# RFSens.net
KiCad netlist of a schematic drawn in EAGLE
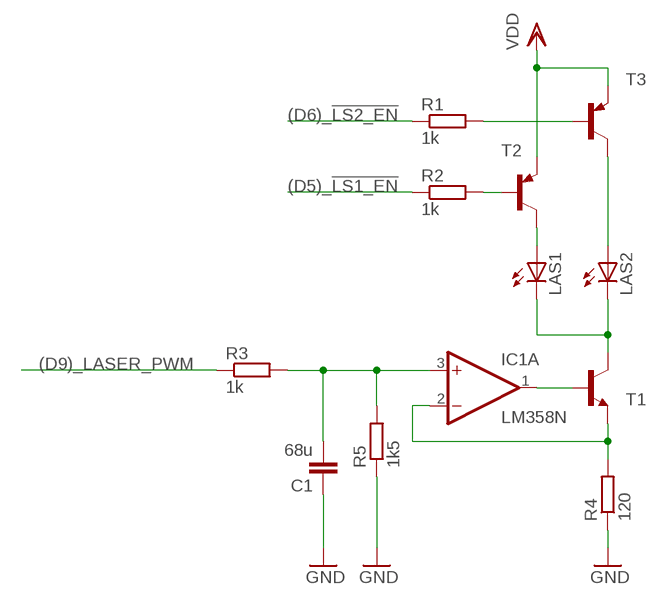
[diagram p0: schematic, sheet 1]

(export (version "E")
  (design (tool "Eeschema 10.0.6"))
  (components
    (comp (ref "C1")
      (value "68u")
      (footprint "eagle-import:C5B3.5")
      (libsource (lib "eagle-import") (part "C5/3.5"))
    )
    (comp (ref "IC1")
      (value "LM358N")
      (footprint "eagle-import:DIL08")
      (libsource (lib "eagle-import") (part "LM358N"))
    )
    (comp (ref "LAS1")
      (value "LED")
      (footprint "eagle-import:SMARTLED-TTW")
      (libsource (lib "eagle-import") (part "LED"))
    )
    (comp (ref "LAS2")
      (value "LED")
      (footprint "eagle-import:SMARTLED-TTW")
      (libsource (lib "eagle-import") (part "LED"))
    )
    (comp (ref "R1")
      (value "1k")
      (footprint "eagle-import:0204_5")
      (libsource (lib "eagle-import") (part "R-EU_0204/5"))
    )
    (comp (ref "R2")
      (value "1k")
      (footprint "eagle-import:0204_5")
      (libsource (lib "eagle-import") (part "R-EU_0204/5"))
    )
    (comp (ref "R3")
      (value "1k")
      (footprint "eagle-import:0204_5")
      (libsource (lib "eagle-import") (part "R-EU_0204/5"))
    )
    (comp (ref "R4")
      (value "120")
      (footprint "eagle-import:0204_5")
      (libsource (lib "eagle-import") (part "R-EU_0204/5"))
    )
    (comp (ref "R5")
      (value "1k5")
      (footprint "eagle-import:0204_5")
      (libsource (lib "eagle-import") (part "R-EU_0204/5"))
    )
    (comp (ref "T1")
      (value "-NPN-SOT89-BCE")
      (footprint "eagle-import:SOT89-BCE")
      (libsource (lib "eagle-import") (part "-NPN-SOT89-BCE"))
    )
    (comp (ref "T2")
      (value "-PNP-SOT23-EBC")
      (footprint "eagle-import:SOT23-EBC")
      (libsource (lib "eagle-import") (part "-PNP-SOT23-EBC"))
    )
    (comp (ref "T3")
      (value "-PNP-SOT23-EBC")
      (footprint "eagle-import:SOT23-EBC")
      (libsource (lib "eagle-import") (part "-PNP-SOT23-EBC"))
    )
  )
  (nets
    (net (code "1") (name "/(D5)_~{LS1_EN}") (class "Default")
      (node (ref "R2") (pin "1") (pinfunction "1_1") (pintype "passive"))
    )
    (net (code "2") (name "/(D6)_~{LS2_EN}") (class "Default")
      (node (ref "R1") (pin "1") (pinfunction "1_1") (pintype "passive"))
    )
    (net (code "3") (name "/(D9)_LASER_PWM") (class "Default")
      (node (ref "R3") (pin "1") (pinfunction "1_1") (pintype "passive"))
    )
    (net (code "4") (name "GND") (class "Default")
      (node (ref "C1") (pin "1") (pinfunction "1_1") (pintype "passive"))
      (node (ref "R4") (pin "1") (pinfunction "1_1") (pintype "passive"))
      (node (ref "R5") (pin "1") (pinfunction "1_1") (pintype "passive"))
    )
    (net (code "5") (name "Net-(IC1A-+IN)") (class "Default")
      (node (ref "C1") (pin "2") (pinfunction "2_2") (pintype "passive"))
      (node (ref "IC1") (pin "3") (pinfunction "+IN_3") (pintype "input"))
      (node (ref "R3") (pin "2") (pinfunction "2_2") (pintype "passive"))
      (node (ref "R5") (pin "2") (pinfunction "2_2") (pintype "passive"))
    )
    (net (code "6") (name "Net-(IC1A--IN)") (class "Default")
      (node (ref "IC1") (pin "2") (pinfunction "-IN_2") (pintype "input"))
      (node (ref "R4") (pin "2") (pinfunction "2_2") (pintype "passive"))
      (node (ref "T1") (pin "E") (pinfunction "E_E") (pintype "passive"))
    )
    (net (code "7") (name "Net-(IC1A-OUT)") (class "Default")
      (node (ref "IC1") (pin "1") (pinfunction "OUT_1") (pintype "output"))
      (node (ref "T1") (pin "B") (pinfunction "B_B") (pintype "passive"))
    )
    (net (code "8") (name "Net-(LAS1-A)") (class "Default")
      (node (ref "LAS1") (pin "A@1") (pinfunction "A_A@1") (pintype "passive"))
      (node (ref "T2") (pin "C") (pinfunction "C_C") (pintype "passive"))
    )
    (net (code "9") (name "Net-(LAS1-C)") (class "Default")
      (node (ref "LAS1") (pin "C@1") (pinfunction "C_C@1") (pintype "passive"))
      (node (ref "LAS2") (pin "C@1") (pinfunction "C_C@1") (pintype "passive"))
      (node (ref "T1") (pin "C") (pinfunction "C_C") (pintype "passive"))
    )
    (net (code "10") (name "Net-(LAS2-A)") (class "Default")
      (node (ref "LAS2") (pin "A@1") (pinfunction "A_A@1") (pintype "passive"))
      (node (ref "T3") (pin "C") (pinfunction "C_C") (pintype "passive"))
    )
    (net (code "11") (name "Net-(R1-Pad2)") (class "Default")
      (node (ref "R1") (pin "2") (pinfunction "2_2") (pintype "passive"))
      (node (ref "T3") (pin "B") (pinfunction "B_B") (pintype "passive"))
    )
    (net (code "12") (name "Net-(R2-Pad2)") (class "Default")
      (node (ref "R2") (pin "2") (pinfunction "2_2") (pintype "passive"))
      (node (ref "T2") (pin "B") (pinfunction "B_B") (pintype "passive"))
    )
    (net (code "13") (name "VDD") (class "Default")
      (node (ref "T2") (pin "E") (pinfunction "E_E") (pintype "passive"))
      (node (ref "T3") (pin "E") (pinfunction "E_E") (pintype "passive"))
    )
  )
)
